# Sch_FindeCarrera.net
KiCad netlist of a schematic drawn in Altium Designer
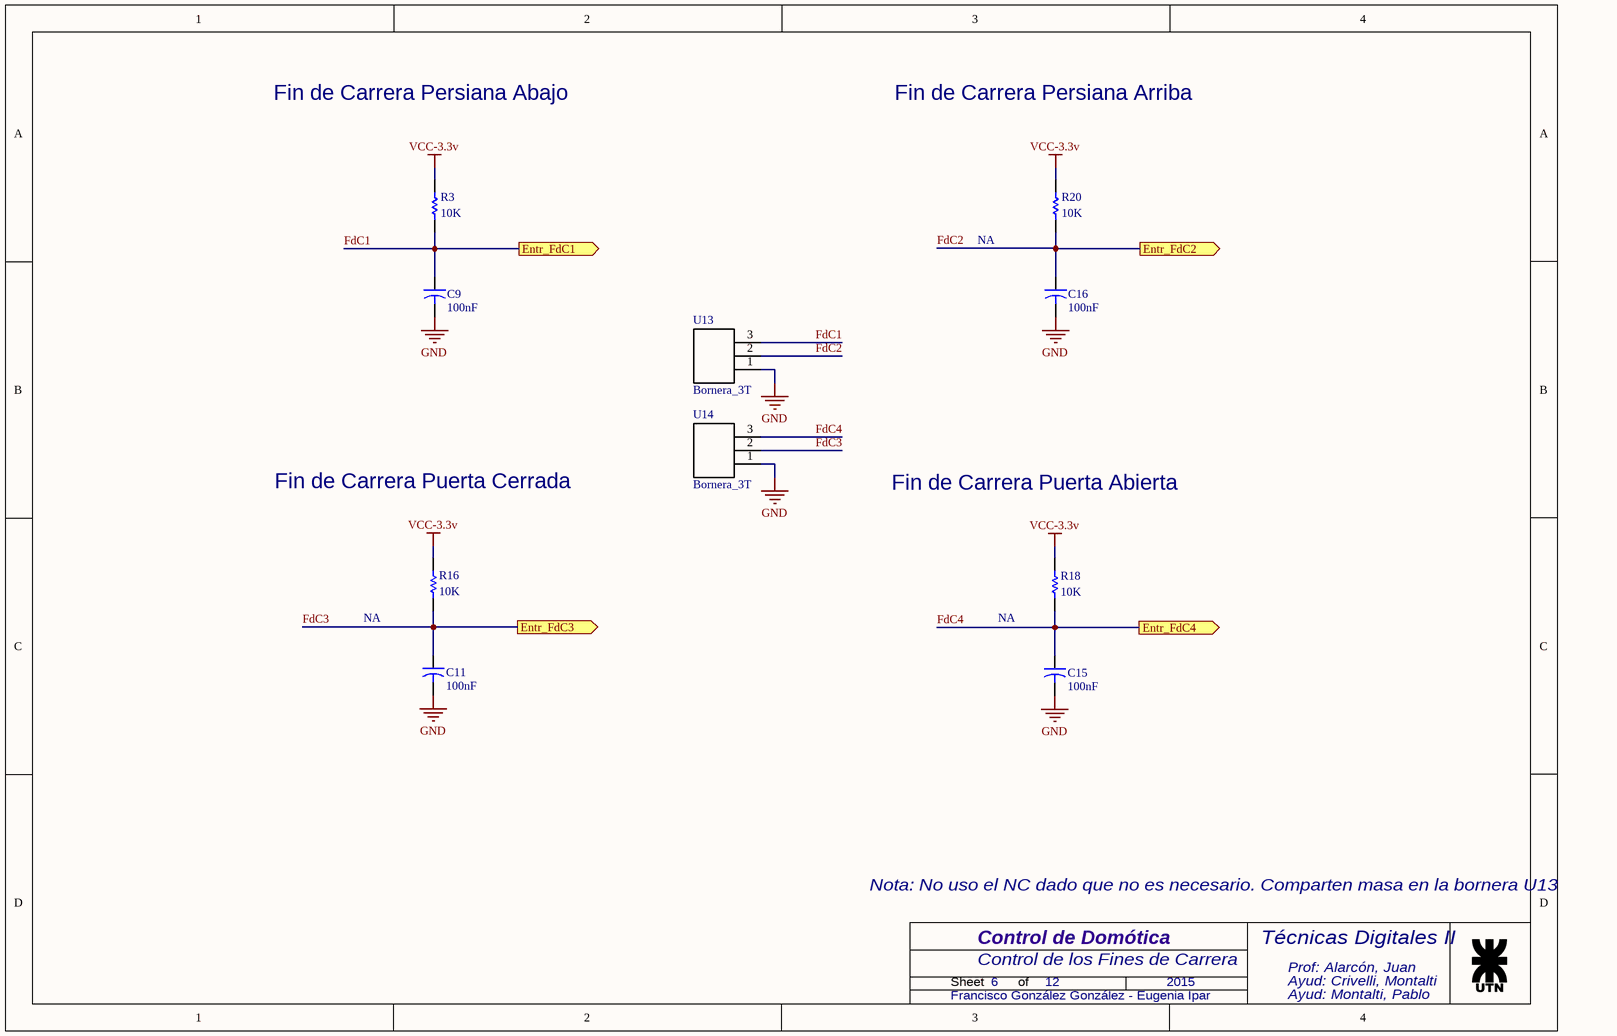
[diagram p0: Sch_FindeCarrera.SchDoc]

(export (version "E")
  (design (tool "Eeschema 10.0.6"))
  (components
    (comp (ref "C9")
      (value "100nF")
      (footprint "CAPR5-4X5")
      (description "Capacitor")
      (fields (field (name "Comment") "Cap2") (field (name "PUBLISHER") "Altium Limited"))
      (libsource (lib "Miscellaneous Devices") (part "Cap2"))
    )
    (comp (ref "C11")
      (value "100nF")
      (footprint "CAPR5-4X5")
      (description "Capacitor")
      (fields (field (name "Comment") "Cap2") (field (name "PUBLISHER") "Altium Limited"))
      (libsource (lib "Miscellaneous Devices") (part "Cap2"))
    )
    (comp (ref "C15")
      (value "100nF")
      (footprint "CAPR5-4X5")
      (description "Capacitor")
      (fields (field (name "Comment") "Cap2") (field (name "PUBLISHER") "Altium Limited"))
      (libsource (lib "Miscellaneous Devices") (part "Cap2"))
    )
    (comp (ref "C16")
      (value "100nF")
      (footprint "CAPR5-4X5")
      (description "Capacitor")
      (fields (field (name "Comment") "Cap2") (field (name "PUBLISHER") "Altium Limited"))
      (libsource (lib "Miscellaneous Devices") (part "Cap2"))
    )
    (comp (ref "R3")
      (value "10K")
      (footprint "AXIAL-0.3")
      (description "Resistor")
      (fields (field (name "Comment") "Res1") (field (name "PUBLISHER") "Altium Limited"))
      (libsource (lib "Miscellaneous Devices") (part "Res1"))
    )
    (comp (ref "R16")
      (value "10K")
      (footprint "AXIAL-0.3")
      (description "Resistor")
      (fields (field (name "Comment") "Res1") (field (name "PUBLISHER") "Altium Limited"))
      (libsource (lib "Miscellaneous Devices") (part "Res1"))
    )
    (comp (ref "R18")
      (value "10K")
      (footprint "AXIAL-0.3")
      (description "Resistor")
      (fields (field (name "Comment") "Res1") (field (name "PUBLISHER") "Altium Limited"))
      (libsource (lib "Miscellaneous Devices") (part "Res1"))
    )
    (comp (ref "R20")
      (value "10K")
      (footprint "AXIAL-0.3")
      (description "Resistor")
      (fields (field (name "Comment") "Res1") (field (name "PUBLISHER") "Altium Limited"))
      (libsource (lib "Miscellaneous Devices") (part "Res1"))
    )
    (comp (ref "U13")
      (value "Bornera_3T")
      (footprint "BORNERA_3")
      (description "Bornera de 3 Terminales Pitch 5mm")
      (libsource (lib "Ampli_Lib_Sch") (part "Bornera_3T"))
    )
    (comp (ref "U14")
      (value "Bornera_3T")
      (footprint "BORNERA_3")
      (description "Bornera de 3 Terminales Pitch 5mm")
      (libsource (lib "Ampli_Lib_Sch") (part "Bornera_3T"))
    )
  )
  (nets
    (net (code "1") (name "/FdC1") (class "Default")
      (node (ref "C9") (pin "1") (pinfunction "1_1") (pintype "passive"))
      (node (ref "R3") (pin "1") (pinfunction "1_1") (pintype "passive"))
      (node (ref "U13") (pin "3") (pinfunction "3_3") (pintype "passive"))
    )
    (net (code "2") (name "/FdC2") (class "Default")
      (node (ref "C16") (pin "1") (pinfunction "1_1") (pintype "passive"))
      (node (ref "R20") (pin "1") (pinfunction "1_1") (pintype "passive"))
      (node (ref "U13") (pin "2") (pinfunction "2_2") (pintype "passive"))
    )
    (net (code "3") (name "/FdC3") (class "Default")
      (node (ref "C11") (pin "1") (pinfunction "1_1") (pintype "passive"))
      (node (ref "R16") (pin "1") (pinfunction "1_1") (pintype "passive"))
      (node (ref "U14") (pin "2") (pinfunction "2_2") (pintype "passive"))
    )
    (net (code "4") (name "/FdC4") (class "Default")
      (node (ref "C15") (pin "1") (pinfunction "1_1") (pintype "passive"))
      (node (ref "R18") (pin "1") (pinfunction "1_1") (pintype "passive"))
      (node (ref "U14") (pin "3") (pinfunction "3_3") (pintype "passive"))
    )
    (net (code "5") (name "GND") (class "Default")
      (node (ref "C11") (pin "2") (pinfunction "2_2") (pintype "passive"))
      (node (ref "C15") (pin "2") (pinfunction "2_2") (pintype "passive"))
      (node (ref "C16") (pin "2") (pinfunction "2_2") (pintype "passive"))
      (node (ref "C9") (pin "2") (pinfunction "2_2") (pintype "passive"))
      (node (ref "U13") (pin "1") (pinfunction "1_1") (pintype "passive"))
      (node (ref "U14") (pin "1") (pinfunction "1_1") (pintype "passive"))
    )
    (net (code "6") (name "VCC-3.3v") (class "Default")
      (node (ref "R16") (pin "2") (pinfunction "2_2") (pintype "passive"))
      (node (ref "R18") (pin "2") (pinfunction "2_2") (pintype "passive"))
      (node (ref "R20") (pin "2") (pinfunction "2_2") (pintype "passive"))
      (node (ref "R3") (pin "2") (pinfunction "2_2") (pintype "passive"))
    )
  )
)
